# external_devices.net
KiCad netlist of a schematic drawn in Altium Designer
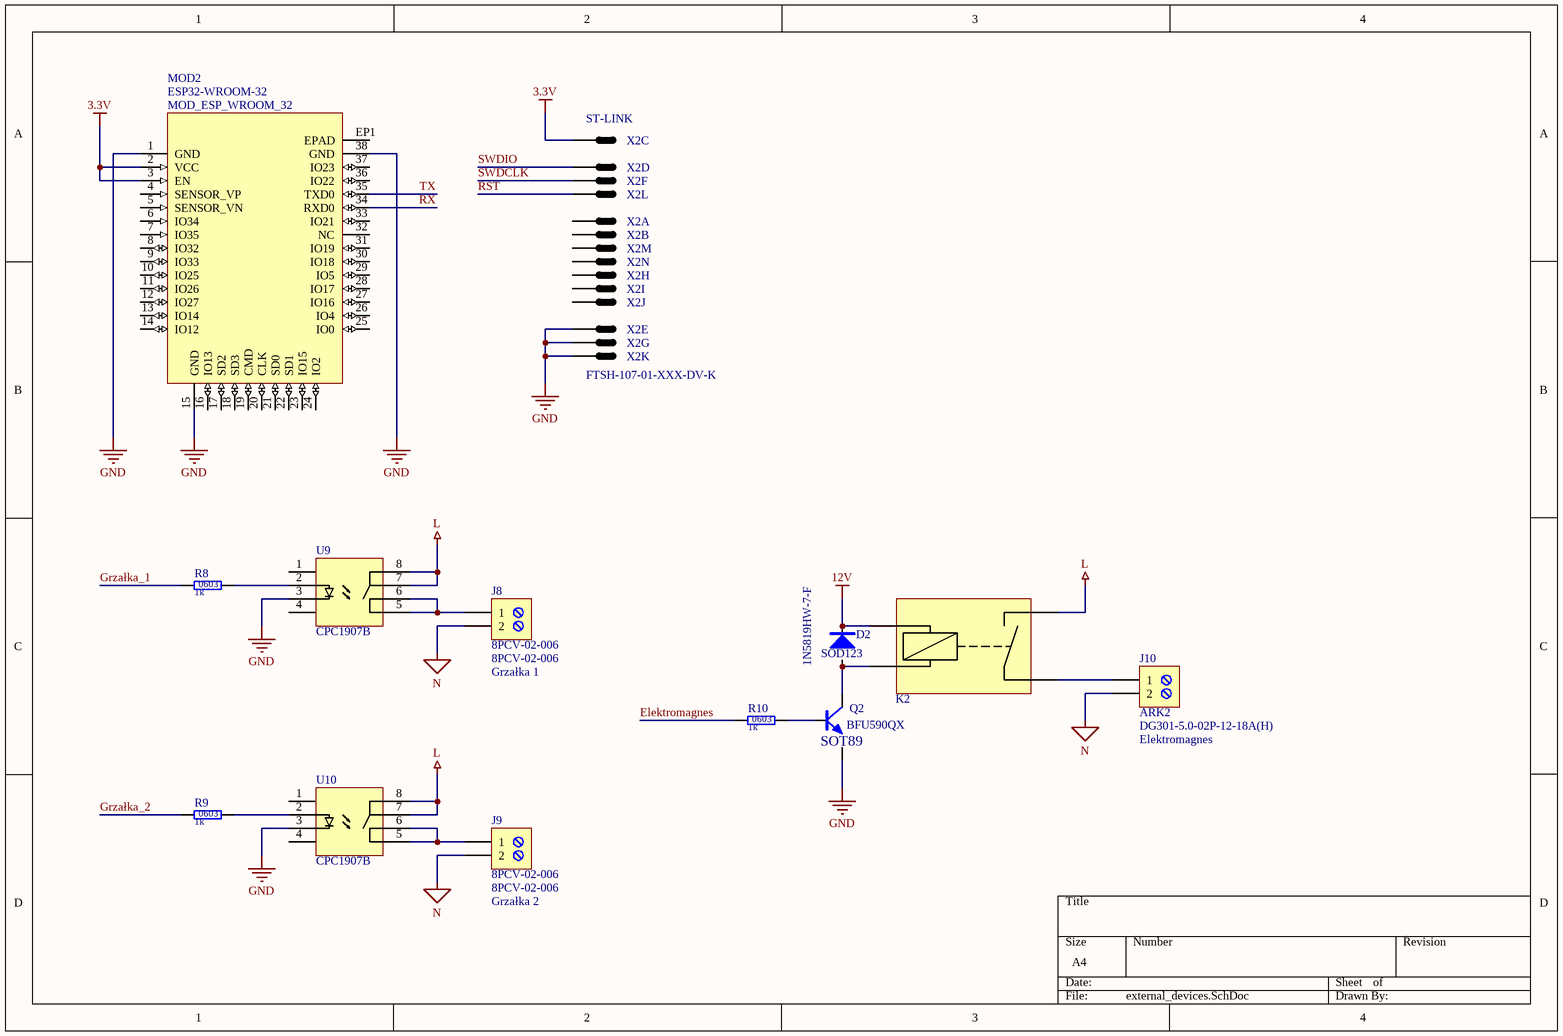
[diagram p0: external_devices.SchDoc]

(export (version "E")
  (design (tool "Eeschema 10.0.6"))
  (components
    (comp (ref "D2")
      (value "1N5819HW-7-F")
      (footprint "SOD123")
      (fields
        (field (name "SCH_FOOTPRINT") "SOD123")
        (field (name "PART NUMBER") "D_1N5819HW_1A_40V_SOD123")
        (field (name "VOLTAGE") "40V")
        (field (name "MANUFACTURER") "Diodes Inc")
      )
      (libsource (lib "Library") (part "D"))
    )
    (comp (ref "J8")
      (value "8PCV-02-006")
      (footprint "J_8PCV-02-006")
      (description "ARK Screw terminal, 2-Pin")
      (fields
        (field (name "SCH_FOOTPRINT") "8PCV-02-006")
        (field (name "PART NUMBER") "J_8PCV-02-006")
        (field (name "MANUFACTURER") "TE Connectivity")
      )
      (libsource (lib "Library") (part "J_ARK2"))
    )
    (comp (ref "J9")
      (value "8PCV-02-006")
      (footprint "J_8PCV-02-006")
      (description "ARK Screw terminal, 2-Pin")
      (fields
        (field (name "SCH_FOOTPRINT") "8PCV-02-006")
        (field (name "PART NUMBER") "J_8PCV-02-006")
        (field (name "MANUFACTURER") "TE Connectivity")
      )
      (libsource (lib "Library") (part "J_ARK2"))
    )
    (comp (ref "J10")
      (value "DG301-5.0-02P-12-18A(H)")
      (footprint "J_ARK2")
      (description "ARK Screw terminal, 2-Pin")
      (fields
        (field (name "SCH_FOOTPRINT") "ARK2")
        (field (name "PART NUMBER") "J_TB-5.0-P-2P")
        (field (name "MANUFACTURER") "DEGSON ELECTRONICS")
      )
      (libsource (lib "Library") (part "J_ARK2"))
    )
    (comp (ref "K2")
      (value "FTR-F3AA012E")
      (footprint "FTR-F3AA012E")
      (libsource (lib "SchLib") (part "FTR-F3AA012E"))
    )
    (comp (ref "MOD2")
      (value "ESP32-WROOM-32")
      (footprint "MOD_ESP_WROOM_32")
      (fields
        (field (name "SCH_FOOTPRINT") "MOD_ESP_WROOM_32")
        (field (name "PART NUMBER") "MOD_ESP32-WROOM-32")
        (field (name "MANUFACTURER") "ESPRESSIF")
        (field (name "Comment") "2.4 GHz Wi-Fi-and-Bluetooth combo chip")
      )
      (libsource (lib "Library") (part "MOD_ESP_WROOM_32"))
    )
    (comp (ref "Q2")
      (value "BFU590QX")
      (footprint "SOT89_TO-243AA_N")
      (fields
        (field (name "SCH_FOOTPRINT") "SOT89")
        (field (name "PART NUMBER") "QNP_BFU590QX")
        (field (name "VOLTAGE") "12V")
        (field (name "MANUFACTURER") "NXP")
      )
      (libsource (lib "Library") (part "QNP_ECB"))
    )
    (comp (ref "R8")
      (value "1k")
      (footprint "R_0603_1608")
      (fields
        (field (name "SCH_FOOTPRINT") "0603")
        (field (name "PART NUMBER") "R_1k_0603_1")
        (field (name "VOLTAGE") "75V")
        (field (name "POWER") "100mW")
      )
      (libsource (lib "Library") (part "R"))
    )
    (comp (ref "R9")
      (value "1k")
      (footprint "R_0603_1608")
      (fields
        (field (name "SCH_FOOTPRINT") "0603")
        (field (name "PART NUMBER") "R_1k_0603_1")
        (field (name "VOLTAGE") "75V")
        (field (name "POWER") "100mW")
      )
      (libsource (lib "Library") (part "R"))
    )
    (comp (ref "R10")
      (value "1k")
      (footprint "R_0603_1608")
      (fields
        (field (name "SCH_FOOTPRINT") "0603")
        (field (name "PART NUMBER") "R_1k_0603_1")
        (field (name "VOLTAGE") "75V")
        (field (name "POWER") "100mW")
      )
      (libsource (lib "Library") (part "R"))
    )
    (comp (ref "U9") (value "CPC1907B") (footprint "CPC1907B") (libsource (lib "SchLib") (part "CPC1907B")))
    (comp (ref "U10") (value "CPC1907B") (footprint "CPC1907B") (libsource (lib "SchLib") (part "CPC1907B")))
    (comp (ref "X2")
      (value "FTSH-107-01-XXX-DV-K")
      (footprint "FTSH-107-01-XXX-DV-K")
      (description "IDC 14pin male connector")
      (libsource (lib "Connectors") (part "FTSH-107-01-XXX-DV-K"))
    )
  )
  (nets
    (net (code "1") (name "/Elektromagnes") (class "Default")
      (node (ref "R10") (pin "1") (pinfunction "1_1") (pintype "passive"))
    )
    (net (code "2") (name "/Grzałka_1") (class "Default")
      (node (ref "R8") (pin "1") (pinfunction "1_1") (pintype "passive"))
    )
    (net (code "3") (name "/Grzałka_2") (class "Default")
      (node (ref "R9") (pin "1") (pinfunction "1_1") (pintype "passive"))
    )
    (net (code "4") (name "/RST") (class "Default")
      (node (ref "X2") (pin "12") (pinfunction "12_12") (pintype "passive"))
    )
    (net (code "5") (name "/RX") (class "Default")
      (node (ref "MOD2") (pin "34") (pinfunction "RXD0_34") (pintype "bidirectional"))
    )
    (net (code "6") (name "/SWDCLK") (class "Default")
      (node (ref "X2") (pin "6") (pinfunction "6_6") (pintype "passive"))
    )
    (net (code "7") (name "/SWDIO") (class "Default")
      (node (ref "X2") (pin "4") (pinfunction "4_4") (pintype "passive"))
    )
    (net (code "8") (name "/TX") (class "Default")
      (node (ref "MOD2") (pin "35") (pinfunction "TXD0_35") (pintype "bidirectional"))
    )
    (net (code "9") (name "3.3V") (class "Default")
      (node (ref "MOD2") (pin "2") (pinfunction "VCC_2") (pintype "input"))
      (node (ref "MOD2") (pin "3") (pinfunction "EN_3") (pintype "input"))
      (node (ref "X2") (pin "3") (pinfunction "3_3") (pintype "passive"))
    )
    (net (code "10") (name "12V") (class "Default")
      (node (ref "D2") (pin "1") (pintype "passive"))
      (node (ref "K2") (pin "1") (pinfunction "1_1") (pintype "passive"))
    )
    (net (code "11") (name "GND") (class "Default")
      (node (ref "MOD2") (pin "1") (pinfunction "GND_1") (pintype "power_in"))
      (node (ref "MOD2") (pin "15") (pinfunction "GND_15") (pintype "power_in"))
      (node (ref "MOD2") (pin "38") (pinfunction "GND_38") (pintype "power_in"))
      (node (ref "Q2") (pin "1") (pinfunction "E_1") (pintype "passive"))
      (node (ref "U10") (pin "3") (pinfunction "3_3") (pintype "passive"))
      (node (ref "U9") (pin "3") (pinfunction "3_3") (pintype "passive"))
      (node (ref "X2") (pin "11") (pinfunction "11_11") (pintype "passive"))
      (node (ref "X2") (pin "5") (pinfunction "5_5") (pintype "passive"))
      (node (ref "X2") (pin "7") (pinfunction "7_7") (pintype "passive"))
    )
    (net (code "12") (name "L") (class "Default")
      (node (ref "K2") (pin "3") (pinfunction "3_3") (pintype "passive"))
      (node (ref "U10") (pin "7") (pinfunction "7_7") (pintype "passive"))
      (node (ref "U10") (pin "8") (pinfunction "8_8") (pintype "passive"))
      (node (ref "U9") (pin "7") (pinfunction "7_7") (pintype "passive"))
      (node (ref "U9") (pin "8") (pinfunction "8_8") (pintype "passive"))
    )
    (net (code "13") (name "N") (class "Default")
      (node (ref "J10") (pin "2") (pinfunction "2_2") (pintype "passive"))
      (node (ref "J8") (pin "2") (pinfunction "2_2") (pintype "passive"))
      (node (ref "J9") (pin "2") (pinfunction "2_2") (pintype "passive"))
    )
    (net (code "14") (name "Net-(J8-Pad1)") (class "Default")
      (node (ref "J8") (pin "1") (pinfunction "1_1") (pintype "passive"))
      (node (ref "U9") (pin "5") (pinfunction "5_5") (pintype "passive"))
      (node (ref "U9") (pin "6") (pinfunction "6_6") (pintype "passive"))
    )
    (net (code "15") (name "Net-(J9-Pad1)") (class "Default")
      (node (ref "J9") (pin "1") (pinfunction "1_1") (pintype "passive"))
      (node (ref "U10") (pin "5") (pinfunction "5_5") (pintype "passive"))
      (node (ref "U10") (pin "6") (pinfunction "6_6") (pintype "passive"))
    )
    (net (code "16") (name "Net-(J10-Pad1)") (class "Default")
      (node (ref "J10") (pin "1") (pinfunction "1_1") (pintype "passive"))
      (node (ref "K2") (pin "4") (pinfunction "4_4") (pintype "passive"))
    )
    (net (code "17") (name "Net-(Q2-B)") (class "Default")
      (node (ref "Q2") (pin "3") (pinfunction "B_3") (pintype "passive"))
      (node (ref "R10") (pin "2") (pinfunction "2_2") (pintype "passive"))
    )
    (net (code "18") (name "Net-(Q2-C)") (class "Default")
      (node (ref "D2") (pin "2") (pintype "passive"))
      (node (ref "K2") (pin "2") (pinfunction "2_2") (pintype "passive"))
      (node (ref "Q2") (pin "2") (pinfunction "C_2") (pintype "passive"))
    )
    (net (code "19") (name "Net-(R8-Pad2)") (class "Default")
      (node (ref "R8") (pin "2") (pinfunction "2_2") (pintype "passive"))
      (node (ref "U9") (pin "2") (pinfunction "2_2") (pintype "passive"))
    )
    (net (code "20") (name "Net-(R9-Pad2)") (class "Default")
      (node (ref "R9") (pin "2") (pinfunction "2_2") (pintype "passive"))
      (node (ref "U10") (pin "2") (pinfunction "2_2") (pintype "passive"))
    )
    (net (code "21") (name "unconnected-(MOD2-CLK-Pad20)") (class "Default")
      (node (ref "MOD2") (pin "20") (pinfunction "CLK_20") (pintype "bidirectional"))
    )
    (net (code "22") (name "unconnected-(MOD2-CMD-Pad19)") (class "Default")
      (node (ref "MOD2") (pin "19") (pinfunction "CMD_19") (pintype "bidirectional"))
    )
    (net (code "23") (name "unconnected-(MOD2-EPAD-PadEP1)") (class "Default")
      (node (ref "MOD2") (pin "EP1") (pinfunction "EPAD_EP1") (pintype "power_in"))
    )
    (net (code "24") (name "unconnected-(MOD2-IO0-Pad25)") (class "Default")
      (node (ref "MOD2") (pin "25") (pinfunction "IO0_25") (pintype "bidirectional"))
    )
    (net (code "25") (name "unconnected-(MOD2-IO2-Pad24)") (class "Default")
      (node (ref "MOD2") (pin "24") (pinfunction "IO2_24") (pintype "bidirectional"))
    )
    (net (code "26") (name "unconnected-(MOD2-IO4-Pad26)") (class "Default")
      (node (ref "MOD2") (pin "26") (pinfunction "IO4_26") (pintype "bidirectional"))
    )
    (net (code "27") (name "unconnected-(MOD2-IO5-Pad29)") (class "Default")
      (node (ref "MOD2") (pin "29") (pinfunction "IO5_29") (pintype "bidirectional"))
    )
    (net (code "28") (name "unconnected-(MOD2-IO12-Pad14)") (class "Default")
      (node (ref "MOD2") (pin "14") (pinfunction "IO12_14") (pintype "bidirectional"))
    )
    (net (code "29") (name "unconnected-(MOD2-IO13-Pad16)") (class "Default")
      (node (ref "MOD2") (pin "16") (pinfunction "IO13_16") (pintype "bidirectional"))
    )
    (net (code "30") (name "unconnected-(MOD2-IO14-Pad13)") (class "Default")
      (node (ref "MOD2") (pin "13") (pinfunction "IO14_13") (pintype "bidirectional"))
    )
    (net (code "31") (name "unconnected-(MOD2-IO15-Pad23)") (class "Default")
      (node (ref "MOD2") (pin "23") (pinfunction "IO15_23") (pintype "bidirectional"))
    )
    (net (code "32") (name "unconnected-(MOD2-IO16-Pad27)") (class "Default")
      (node (ref "MOD2") (pin "27") (pinfunction "IO16_27") (pintype "bidirectional"))
    )
    (net (code "33") (name "unconnected-(MOD2-IO17-Pad28)") (class "Default")
      (node (ref "MOD2") (pin "28") (pinfunction "IO17_28") (pintype "bidirectional"))
    )
    (net (code "34") (name "unconnected-(MOD2-IO18-Pad30)") (class "Default")
      (node (ref "MOD2") (pin "30") (pinfunction "IO18_30") (pintype "bidirectional"))
    )
    (net (code "35") (name "unconnected-(MOD2-IO19-Pad31)") (class "Default")
      (node (ref "MOD2") (pin "31") (pinfunction "IO19_31") (pintype "bidirectional"))
    )
    (net (code "36") (name "unconnected-(MOD2-IO21-Pad33)") (class "Default")
      (node (ref "MOD2") (pin "33") (pinfunction "IO21_33") (pintype "bidirectional"))
    )
    (net (code "37") (name "unconnected-(MOD2-IO22-Pad36)") (class "Default")
      (node (ref "MOD2") (pin "36") (pinfunction "IO22_36") (pintype "bidirectional"))
    )
    (net (code "38") (name "unconnected-(MOD2-IO23-Pad37)") (class "Default")
      (node (ref "MOD2") (pin "37") (pinfunction "IO23_37") (pintype "bidirectional"))
    )
    (net (code "39") (name "unconnected-(MOD2-IO25-Pad10)") (class "Default")
      (node (ref "MOD2") (pin "10") (pinfunction "IO25_10") (pintype "bidirectional"))
    )
    (net (code "40") (name "unconnected-(MOD2-IO26-Pad11)") (class "Default")
      (node (ref "MOD2") (pin "11") (pinfunction "IO26_11") (pintype "bidirectional"))
    )
    (net (code "41") (name "unconnected-(MOD2-IO27-Pad12)") (class "Default")
      (node (ref "MOD2") (pin "12") (pinfunction "IO27_12") (pintype "bidirectional"))
    )
    (net (code "42") (name "unconnected-(MOD2-IO32-Pad8)") (class "Default")
      (node (ref "MOD2") (pin "8") (pinfunction "IO32_8") (pintype "bidirectional"))
    )
    (net (code "43") (name "unconnected-(MOD2-IO33-Pad9)") (class "Default")
      (node (ref "MOD2") (pin "9") (pinfunction "IO33_9") (pintype "bidirectional"))
    )
    (net (code "44") (name "unconnected-(MOD2-IO34-Pad6)") (class "Default")
      (node (ref "MOD2") (pin "6") (pinfunction "IO34_6") (pintype "input"))
    )
    (net (code "45") (name "unconnected-(MOD2-IO35-Pad7)") (class "Default")
      (node (ref "MOD2") (pin "7") (pinfunction "IO35_7") (pintype "input"))
    )
    (net (code "46") (name "unconnected-(MOD2-NC-Pad32)") (class "Default")
      (node (ref "MOD2") (pin "32") (pinfunction "NC_32") (pintype "passive"))
    )
    (net (code "47") (name "unconnected-(MOD2-SD0-Pad21)") (class "Default")
      (node (ref "MOD2") (pin "21") (pinfunction "SD0_21") (pintype "bidirectional"))
    )
    (net (code "48") (name "unconnected-(MOD2-SD1-Pad22)") (class "Default")
      (node (ref "MOD2") (pin "22") (pinfunction "SD1_22") (pintype "bidirectional"))
    )
    (net (code "49") (name "unconnected-(MOD2-SD2-Pad17)") (class "Default")
      (node (ref "MOD2") (pin "17") (pinfunction "SD2_17") (pintype "bidirectional"))
    )
    (net (code "50") (name "unconnected-(MOD2-SD3-Pad18)") (class "Default")
      (node (ref "MOD2") (pin "18") (pinfunction "SD3_18") (pintype "bidirectional"))
    )
    (net (code "51") (name "unconnected-(MOD2-SENSOR_VN-Pad5)") (class "Default")
      (node (ref "MOD2") (pin "5") (pinfunction "SENSOR_VN_5") (pintype "input"))
    )
    (net (code "52") (name "unconnected-(MOD2-SENSOR_VP-Pad4)") (class "Default")
      (node (ref "MOD2") (pin "4") (pinfunction "SENSOR_VP_4") (pintype "input"))
    )
    (net (code "53") (name "unconnected-(U9-Pad1)") (class "Default")
      (node (ref "U9") (pin "1") (pinfunction "1_1") (pintype "passive"))
    )
    (net (code "54") (name "unconnected-(U9-Pad4)") (class "Default")
      (node (ref "U9") (pin "4") (pinfunction "4_4") (pintype "passive"))
    )
    (net (code "55") (name "unconnected-(U10-Pad1)") (class "Default")
      (node (ref "U10") (pin "1") (pinfunction "1_1") (pintype "passive"))
    )
    (net (code "56") (name "unconnected-(U10-Pad4)") (class "Default")
      (node (ref "U10") (pin "4") (pinfunction "4_4") (pintype "passive"))
    )
    (net (code "57") (name "unconnected-(X2-Pad1)") (class "Default")
      (node (ref "X2") (pin "1") (pinfunction "1_1") (pintype "passive"))
    )
    (net (code "58") (name "unconnected-(X2-Pad2)") (class "Default")
      (node (ref "X2") (pin "2") (pinfunction "2_2") (pintype "passive"))
    )
    (net (code "59") (name "unconnected-(X2-Pad8)") (class "Default")
      (node (ref "X2") (pin "8") (pinfunction "8_8") (pintype "passive"))
    )
    (net (code "60") (name "unconnected-(X2-Pad9)") (class "Default")
      (node (ref "X2") (pin "9") (pinfunction "9_9") (pintype "passive"))
    )
    (net (code "61") (name "unconnected-(X2-Pad10)") (class "Default")
      (node (ref "X2") (pin "10") (pinfunction "10_10") (pintype "passive"))
    )
    (net (code "62") (name "unconnected-(X2-Pad13)") (class "Default")
      (node (ref "X2") (pin "13") (pinfunction "13_13") (pintype "passive"))
    )
    (net (code "63") (name "unconnected-(X2-Pad14)") (class "Default")
      (node (ref "X2") (pin "14") (pinfunction "14_14") (pintype "passive"))
    )
  )
)
